# breakout.net
KiCad netlist of a schematic drawn in Altium Designer
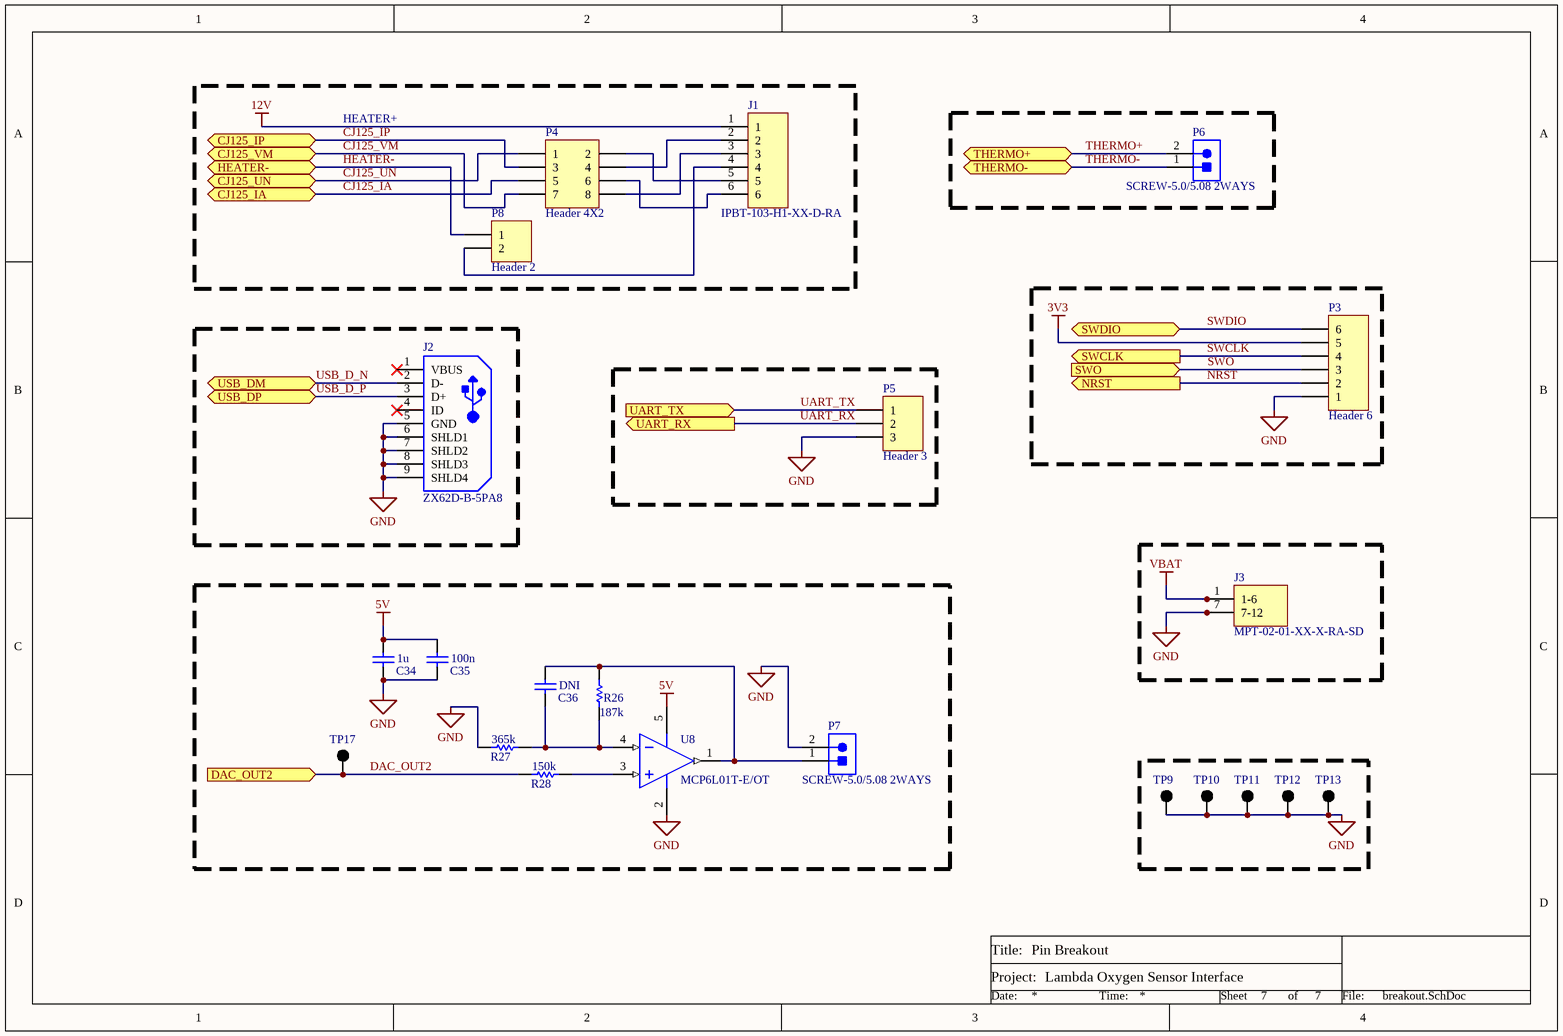
[diagram p0: breakout.SchDoc]

(export (version "E")
  (design (tool "Eeschema 10.0.6"))
  (components
    (comp (ref "C34")
      (value "1u")
      (footprint "1206")
      (description "Generic 1206 Capacitor")
      (libsource (lib "symbol_library") (part "C_1206"))
    )
    (comp (ref "C35")
      (value "100n")
      (footprint "0805")
      (description "Generic 0805 Capacitor")
      (libsource (lib "symbol_library") (part "C_0805"))
    )
    (comp (ref "C36")
      (value "DNI")
      (footprint "0805")
      (description "Generic 0805 Capacitor")
      (libsource (lib "symbol_library") (part "C_0805"))
    )
    (comp (ref "J1")
      (value "IPBT-103-H1-XX-D-RA")
      (footprint "IPBT-103-H1-XX-D-RA")
      (description "0.165 INCH DOUBLE ROW TERMINAL ASSEMBLY")
      (libsource (lib "symbol_library") (part "IPBT-103-H1-XX-D-RA"))
    )
    (comp (ref "J2")
      (value "ZX62D-B-5PA8")
      (footprint "HIRO-ZX62D-B-5PA8_V")
      (description "Micro-USB Connector Meeting USB 2.0 Standard, -30 to 85 degC, 5-Pin SMD, RoHS, Tape and Reel")
      (fields (field (name "MANUFACTURER") "HiroseElectric"))
      (libsource (lib "symbol_library") (part "Micro_USB"))
    )
    (comp (ref "J3")
      (value "MPT-02-01-XX-X-RA-SD")
      (footprint "MPT-02-01-XX-X-RA-SD")
      (libsource (lib "symbol_library") (part "MPT-02-01-XX-X-RA-SD"))
    )
    (comp (ref "P3")
      (value "Header 6")
      (footprint "HDR1X6")
      (description "Header, 6-Pin")
      (fields (field (name "PUBLISHER") "Altium Limited"))
      (libsource (lib "Miscellaneous Connectors") (part "Header 6"))
    )
    (comp (ref "P4")
      (value "Header 4X2")
      (footprint "HDR2X4")
      (description "Header, 4-Pin, Dual row")
      (fields (field (name "PUBLISHER") "Altium Limited"))
      (libsource (lib "Miscellaneous Connectors") (part "Header 4X2"))
    )
    (comp (ref "P5")
      (value "Header 3")
      (footprint "HDR1X3")
      (description "Header, 3-Pin")
      (fields (field (name "PUBLISHER") "Altium Limited"))
      (libsource (lib "Miscellaneous Connectors") (part "Header 3"))
    )
    (comp (ref "P6")
      (value "SCREW-5.0/5.08 2WAYS")
      (footprint "Degson_DG126-5.0-02P-14")
      (description "Socket, Screw Terminal Block, 2 Way, 5.0 mm Pitch, 90 Degree Angle, Through-Hole")
      (fields (field (name "MANUFACTURER") "No Vendor"))
      (libsource (lib "symbol_library") (part "Screw_Header_2"))
    )
    (comp (ref "P7")
      (value "SCREW-5.0/5.08 2WAYS")
      (footprint "Degson_DG126-5.0-02P-14")
      (description "Socket, Screw Terminal Block, 2 Way, 5.0 mm Pitch, 90 Degree Angle, Through-Hole")
      (fields (field (name "MANUFACTURER") "No Vendor"))
      (libsource (lib "symbol_library") (part "Screw_Header_2"))
    )
    (comp (ref "P8")
      (value "Header 2")
      (footprint "HDR1X2")
      (description "Header, 2-Pin")
      (fields (field (name "PUBLISHER") "Altium Limited"))
      (libsource (lib "Miscellaneous Connectors") (part "Header 2"))
    )
    (comp (ref "R26")
      (value "187k")
      (footprint "0603")
      (description "Generic 0603 Resistor")
      (libsource (lib "symbol_library") (part "R_0603"))
    )
    (comp (ref "R27")
      (value "365k")
      (footprint "0603")
      (description "Generic 0603 Resistor")
      (libsource (lib "symbol_library") (part "R_0603"))
    )
    (comp (ref "R28")
      (value "150k")
      (footprint "0603")
      (description "Generic 0603 Resistor")
      (libsource (lib "symbol_library") (part "R_0603"))
    )
    (comp (ref "TP9")
      (value "5001")
      (footprint "KSTN-5001")
      (description "Test Point, Black, 1-Pin THD, RoHS, Bulk")
      (fields (field (name "MANUFACTURER") "Keystone"))
      (libsource (lib "symbol_library") (part "TP5001"))
    )
    (comp (ref "TP10")
      (value "5001")
      (footprint "KSTN-5001")
      (description "Test Point, Black, 1-Pin THD, RoHS, Bulk")
      (fields (field (name "MANUFACTURER") "Keystone"))
      (libsource (lib "symbol_library") (part "TP5001"))
    )
    (comp (ref "TP11")
      (value "5001")
      (footprint "KSTN-5001")
      (description "Test Point, Black, 1-Pin THD, RoHS, Bulk")
      (fields (field (name "MANUFACTURER") "Keystone"))
      (libsource (lib "symbol_library") (part "TP5001"))
    )
    (comp (ref "TP12")
      (value "5001")
      (footprint "KSTN-5001")
      (description "Test Point, Black, 1-Pin THD, RoHS, Bulk")
      (fields (field (name "MANUFACTURER") "Keystone"))
      (libsource (lib "symbol_library") (part "TP5001"))
    )
    (comp (ref "TP13")
      (value "5001")
      (footprint "KSTN-5001")
      (description "Test Point, Black, 1-Pin THD, RoHS, Bulk")
      (fields (field (name "MANUFACTURER") "Keystone"))
      (libsource (lib "symbol_library") (part "TP5001"))
    )
    (comp (ref "TP17")
      (value "5001")
      (footprint "KSTN-5001")
      (description "Test Point, Black, 1-Pin THD, RoHS, Bulk")
      (fields (field (name "MANUFACTURER") "Keystone"))
      (libsource (lib "symbol_library") (part "TP5001"))
    )
    (comp (ref "U8")
      (value "MCP6L01T-E/OT")
      (footprint "DDC0005A_M")
      (description "1 MHz, 85 uA Op Amp, 5-Pin SOT-23, Extended Temperature Range")
      (libsource (lib "symbol_library") (part "MCP6L01"))
    )
  )
  (nets
    (net (code "1") (name "/CJ125_IA") (class "Default")
      (node (ref "P4") (pin "5") (pinfunction "5_5") (pintype "passive"))
    )
    (net (code "2") (name "/CJ125_IP") (class "Default")
      (node (ref "P4") (pin "3") (pinfunction "3_3") (pintype "passive"))
    )
    (net (code "3") (name "/CJ125_UN") (class "Default")
      (node (ref "P4") (pin "1") (pinfunction "1_1") (pintype "passive"))
    )
    (net (code "4") (name "/CJ125_VM") (class "Default")
      (node (ref "P4") (pin "7") (pinfunction "7_7") (pintype "passive"))
    )
    (net (code "5") (name "/DAC_OUT2") (class "Default")
      (node (ref "R28") (pin "1") (pinfunction "1_1") (pintype "passive"))
      (node (ref "TP17") (pin "1") (pintype "passive"))
    )
    (net (code "6") (name "/HEATER-") (class "Default")
      (node (ref "P8") (pin "1") (pinfunction "1_1") (pintype "passive"))
    )
    (net (code "7") (name "/NRST") (class "Default")
      (node (ref "P3") (pin "2") (pinfunction "2_2") (pintype "passive"))
    )
    (net (code "8") (name "/SWCLK") (class "Default")
      (node (ref "P3") (pin "4") (pinfunction "4_4") (pintype "passive"))
    )
    (net (code "9") (name "/SWDIO") (class "Default")
      (node (ref "P3") (pin "6") (pinfunction "6_6") (pintype "passive"))
    )
    (net (code "10") (name "/SWO") (class "Default")
      (node (ref "P3") (pin "3") (pinfunction "3_3") (pintype "passive"))
    )
    (net (code "11") (name "/THERMO+") (class "Default")
      (node (ref "P6") (pin "2") (pinfunction "2_2") (pintype "passive"))
    )
    (net (code "12") (name "/THERMO-") (class "Default")
      (node (ref "P6") (pin "1") (pinfunction "1_1") (pintype "passive"))
    )
    (net (code "13") (name "/UART_RX") (class "Default")
      (node (ref "P5") (pin "2") (pinfunction "2_2") (pintype "passive"))
    )
    (net (code "14") (name "/UART_TX") (class "Default")
      (node (ref "P5") (pin "1") (pinfunction "1_1") (pintype "passive"))
    )
    (net (code "15") (name "/USB_D_N") (class "Default")
      (node (ref "J2") (pin "2") (pinfunction "D-_2") (pintype "passive"))
    )
    (net (code "16") (name "/USB_D_P") (class "Default")
      (node (ref "J2") (pin "3") (pinfunction "D+_3") (pintype "passive"))
    )
    (net (code "17") (name "3V3") (class "Default")
      (node (ref "P3") (pin "5") (pinfunction "5_5") (pintype "passive"))
    )
    (net (code "18") (name "5V") (class "Default")
      (node (ref "C34") (pin "2") (pinfunction "2_2") (pintype "passive"))
      (node (ref "C35") (pin "2") (pinfunction "2_2") (pintype "passive"))
      (node (ref "U8") (pin "5") (pinfunction "VDD_5") (pintype "power_in"))
    )
    (net (code "19") (name "12V") (class "Default")
      (node (ref "J1") (pin "1") (pinfunction "1_1") (pintype "passive"))
    )
    (net (code "20") (name "GND") (class "Default")
      (node (ref "C34") (pin "1") (pinfunction "1_1") (pintype "passive"))
      (node (ref "C35") (pin "1") (pinfunction "1_1") (pintype "passive"))
      (node (ref "J2") (pin "5") (pinfunction "GND_5") (pintype "passive"))
      (node (ref "J2") (pin "6") (pinfunction "SHLD1_6") (pintype "passive"))
      (node (ref "J2") (pin "7") (pinfunction "SHLD2_7") (pintype "passive"))
      (node (ref "J2") (pin "8") (pinfunction "SHLD3_8") (pintype "passive"))
      (node (ref "J2") (pin "9") (pinfunction "SHLD4_9") (pintype "passive"))
      (node (ref "J3") (pin "10") (pinfunction "10_10") (pintype "passive"))
      (node (ref "J3") (pin "11") (pinfunction "11_11") (pintype "passive"))
      (node (ref "J3") (pin "12") (pinfunction "12_12") (pintype "passive"))
      (node (ref "J3") (pin "7") (pinfunction "7-12_7") (pintype "passive"))
      (node (ref "J3") (pin "8") (pinfunction "8_8") (pintype "passive"))
      (node (ref "J3") (pin "9") (pinfunction "9_9") (pintype "passive"))
      (node (ref "P3") (pin "1") (pinfunction "1_1") (pintype "passive"))
      (node (ref "P5") (pin "3") (pinfunction "3_3") (pintype "passive"))
      (node (ref "P7") (pin "2") (pinfunction "2_2") (pintype "passive"))
      (node (ref "R27") (pin "1") (pinfunction "1_1") (pintype "passive"))
      (node (ref "TP10") (pin "1") (pintype "passive"))
      (node (ref "TP11") (pin "1") (pintype "passive"))
      (node (ref "TP12") (pin "1") (pintype "passive"))
      (node (ref "TP13") (pin "1") (pintype "passive"))
      (node (ref "TP9") (pin "1") (pintype "passive"))
      (node (ref "U8") (pin "2") (pinfunction "VSS_2") (pintype "power_in"))
    )
    (net (code "21") (name "Net-(J1-Pad2)") (class "Default")
      (node (ref "J1") (pin "2") (pinfunction "2_2") (pintype "passive"))
      (node (ref "P4") (pin "4") (pinfunction "4_4") (pintype "passive"))
    )
    (net (code "22") (name "Net-(J1-Pad3)") (class "Default")
      (node (ref "J1") (pin "3") (pinfunction "3_3") (pintype "passive"))
      (node (ref "P4") (pin "8") (pinfunction "8_8") (pintype "passive"))
    )
    (net (code "23") (name "Net-(J1-Pad4)") (class "Default")
      (node (ref "J1") (pin "4") (pinfunction "4_4") (pintype "passive"))
      (node (ref "P8") (pin "2") (pinfunction "2_2") (pintype "passive"))
    )
    (net (code "24") (name "Net-(J1-Pad5)") (class "Default")
      (node (ref "J1") (pin "5") (pinfunction "5_5") (pintype "passive"))
      (node (ref "P4") (pin "2") (pinfunction "2_2") (pintype "passive"))
    )
    (net (code "25") (name "Net-(J1-Pad6)") (class "Default")
      (node (ref "J1") (pin "6") (pinfunction "6_6") (pintype "passive"))
      (node (ref "P4") (pin "6") (pinfunction "6_6") (pintype "passive"))
    )
    (net (code "26") (name "Net-(U8-VIN+)") (class "Default")
      (node (ref "R28") (pin "2") (pinfunction "2_2") (pintype "passive"))
      (node (ref "U8") (pin "3") (pinfunction "VIN+_3") (pintype "input"))
    )
    (net (code "27") (name "Net-(U8-VIN-)") (class "Default")
      (node (ref "C36") (pin "1") (pinfunction "1_1") (pintype "passive"))
      (node (ref "R26") (pin "1") (pinfunction "1_1") (pintype "passive"))
      (node (ref "R27") (pin "2") (pinfunction "2_2") (pintype "passive"))
      (node (ref "U8") (pin "4") (pinfunction "VIN-_4") (pintype "input"))
    )
    (net (code "28") (name "Net-(U8-VOUT)") (class "Default")
      (node (ref "C36") (pin "2") (pinfunction "2_2") (pintype "passive"))
      (node (ref "P7") (pin "1") (pinfunction "1_1") (pintype "passive"))
      (node (ref "R26") (pin "2") (pinfunction "2_2") (pintype "passive"))
      (node (ref "U8") (pin "1") (pinfunction "VOUT_1") (pintype "output"))
    )
    (net (code "29") (name "VBAT") (class "Default")
      (node (ref "J3") (pin "1") (pinfunction "1-6_1") (pintype "passive"))
      (node (ref "J3") (pin "2") (pinfunction "2_2") (pintype "passive"))
      (node (ref "J3") (pin "3") (pinfunction "3_3") (pintype "passive"))
      (node (ref "J3") (pin "4") (pinfunction "4_4") (pintype "passive"))
      (node (ref "J3") (pin "5") (pinfunction "5_5") (pintype "passive"))
      (node (ref "J3") (pin "6") (pinfunction "6_6") (pintype "passive"))
    )
    (net (code "30") (name "unconnected-(J2-ID-Pad4)") (class "Default")
      (node (ref "J2") (pin "4") (pinfunction "ID_4") (pintype "passive+no_connect"))
    )
    (net (code "31") (name "unconnected-(J2-VBUS-Pad1)") (class "Default")
      (node (ref "J2") (pin "1") (pinfunction "VBUS_1") (pintype "passive+no_connect"))
    )
  )
)
